# Power.net
KiCad netlist of a schematic drawn in Altium Designer
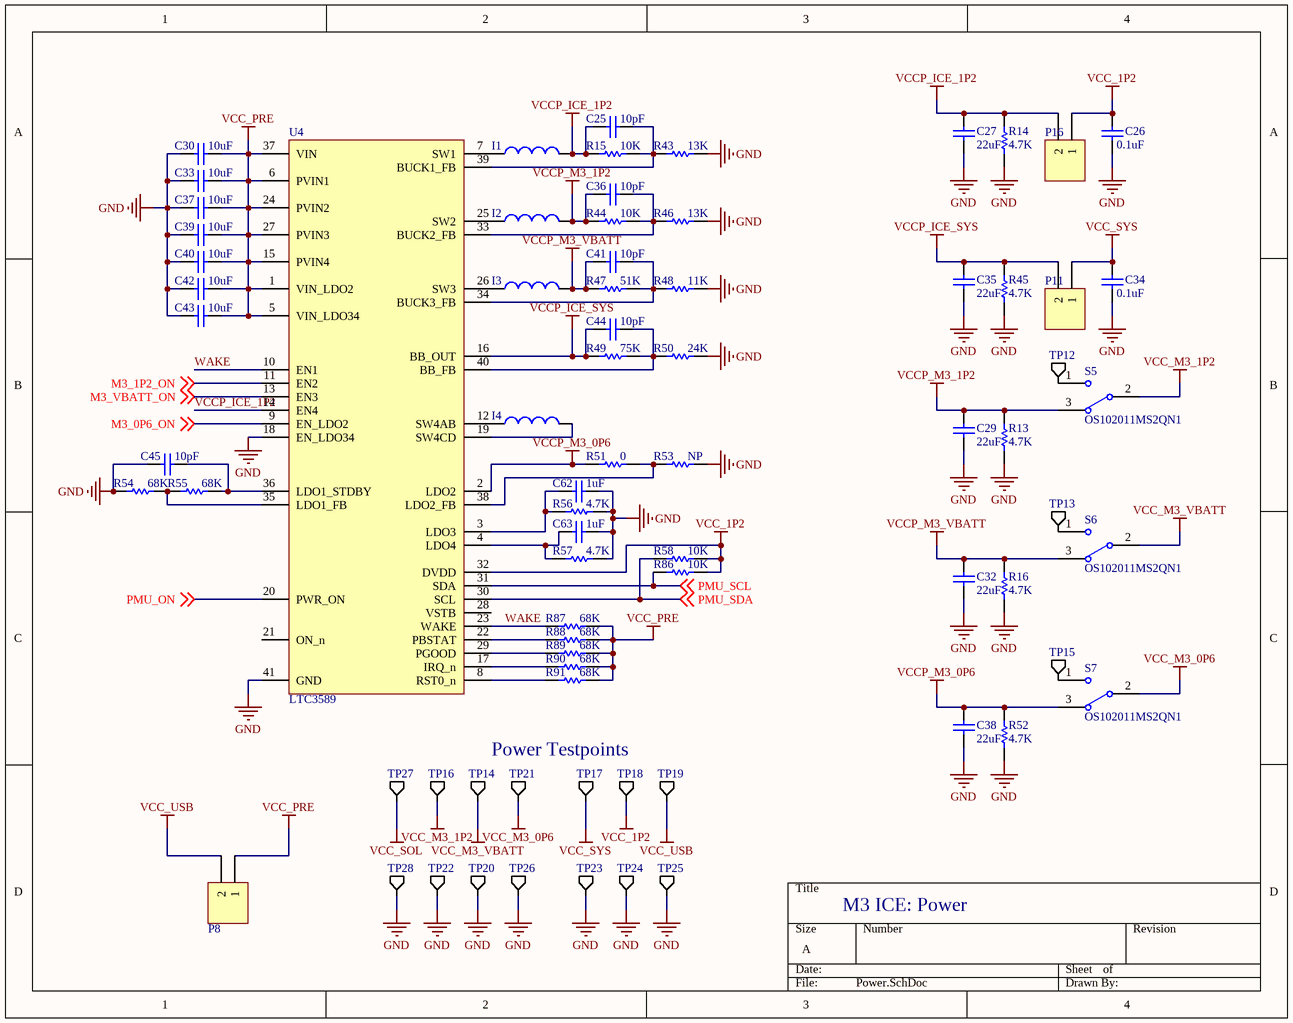
[diagram p0: Power.SchDoc]

(export (version "E")
  (design (tool "Eeschema 10.0.6"))
  (components
    (comp (ref "C25")
      (value "10pF")
      (footprint "0402")
      (description "Capacitor (Semiconductor SIM Model)")
      (fields
        (field (name "DISTPARTNO") "445-1235-1-ND")
        (field (name "MANPARTNO") "C1005C0G1H100D")
        (field (name "PUBLISHER") "Altium Limited")
      )
      (libsource (lib "Miscellaneous Devices") (part "Cap Semi"))
    )
    (comp (ref "C26")
      (value "0.1uF")
      (footprint "1608[0603]")
      (description "Capacitor (Semiconductor SIM Model)")
      (fields
        (field (name "DISTPARTNO") "445-1317-1-ND")
        (field (name "MANPARTNO") "C1608X7R1C104K")
        (field (name "PUBLISHER") "Altium Limited")
      )
      (libsource (lib "Miscellaneous Devices") (part "Cap Semi"))
    )
    (comp (ref "C27")
      (value "22uF")
      (footprint "0805")
      (description "Capacitor (Semiconductor SIM Model)")
      (fields
        (field (name "DISTPARTNO") "587-2782-1-ND")
        (field (name "MANPARTNO") "LMK316AB7226ML-TR")
        (field (name "PUBLISHER") "Altium Limited")
      )
      (libsource (lib "M3") (part "Cap Chip"))
    )
    (comp (ref "C29")
      (value "22uF")
      (footprint "0805")
      (description "Capacitor (Semiconductor SIM Model)")
      (fields
        (field (name "DISTPARTNO") "587-2782-1-ND")
        (field (name "MANPARTNO") "LMK316AB7226ML-TR")
        (field (name "PUBLISHER") "Altium Limited")
      )
      (libsource (lib "M3") (part "Cap Chip"))
    )
    (comp (ref "C30")
      (value "10uF")
      (footprint "0805")
      (description "Capacitor (Semiconductor SIM Model)")
      (fields
        (field (name "DISTPARTNO") "445-6857-1-ND")
        (field (name "MANPARTNO") "C2012X7R1A106K")
        (field (name "PUBLISHER") "Altium Limited")
      )
      (libsource (lib "M3") (part "Cap Chip"))
    )
    (comp (ref "C32")
      (value "22uF")
      (footprint "0805")
      (description "Capacitor (Semiconductor SIM Model)")
      (fields
        (field (name "DISTPARTNO") "587-2782-1-ND")
        (field (name "MANPARTNO") "LMK316AB7226ML-TR")
        (field (name "PUBLISHER") "Altium Limited")
      )
      (libsource (lib "M3") (part "Cap Chip"))
    )
    (comp (ref "C33")
      (value "10uF")
      (footprint "0805")
      (description "Capacitor (Semiconductor SIM Model)")
      (fields
        (field (name "DISTPARTNO") "445-6857-1-ND")
        (field (name "MANPARTNO") "C2012X7R1A106K")
        (field (name "PUBLISHER") "Altium Limited")
      )
      (libsource (lib "M3") (part "Cap Chip"))
    )
    (comp (ref "C34")
      (value "0.1uF")
      (footprint "1608[0603]")
      (description "Capacitor (Semiconductor SIM Model)")
      (fields
        (field (name "DISTPARTNO") "445-1317-1-ND")
        (field (name "MANPARTNO") "C1608X7R1C104K")
        (field (name "PUBLISHER") "Altium Limited")
      )
      (libsource (lib "Miscellaneous Devices") (part "Cap Semi"))
    )
    (comp (ref "C35")
      (value "22uF")
      (footprint "0805")
      (description "Capacitor (Semiconductor SIM Model)")
      (fields
        (field (name "DISTPARTNO") "587-2782-1-ND")
        (field (name "MANPARTNO") "LMK316AB7226ML-TR")
        (field (name "PUBLISHER") "Altium Limited")
      )
      (libsource (lib "M3") (part "Cap Chip"))
    )
    (comp (ref "C36")
      (value "10pF")
      (footprint "0402")
      (description "Capacitor (Semiconductor SIM Model)")
      (fields
        (field (name "DISTPARTNO") "445-1235-1-ND")
        (field (name "MANPARTNO") "C1005C0G1H100D")
        (field (name "PUBLISHER") "Altium Limited")
      )
      (libsource (lib "Miscellaneous Devices") (part "Cap Semi"))
    )
    (comp (ref "C37")
      (value "10uF")
      (footprint "0805")
      (description "Capacitor (Semiconductor SIM Model)")
      (fields
        (field (name "DISTPARTNO") "445-6857-1-ND")
        (field (name "MANPARTNO") "C2012X7R1A106K")
        (field (name "PUBLISHER") "Altium Limited")
      )
      (libsource (lib "M3") (part "Cap Chip"))
    )
    (comp (ref "C38")
      (value "22uF")
      (footprint "0805")
      (description "Capacitor (Semiconductor SIM Model)")
      (fields
        (field (name "DISTPARTNO") "587-2782-1-ND")
        (field (name "MANPARTNO") "LMK316AB7226ML-TR")
        (field (name "PUBLISHER") "Altium Limited")
      )
      (libsource (lib "M3") (part "Cap Chip"))
    )
    (comp (ref "C39")
      (value "10uF")
      (footprint "0805")
      (description "Capacitor (Semiconductor SIM Model)")
      (fields
        (field (name "DISTPARTNO") "445-6857-1-ND")
        (field (name "MANPARTNO") "C2012X7R1A106K")
        (field (name "PUBLISHER") "Altium Limited")
      )
      (libsource (lib "M3") (part "Cap Chip"))
    )
    (comp (ref "C40")
      (value "10uF")
      (footprint "0805")
      (description "Capacitor (Semiconductor SIM Model)")
      (fields
        (field (name "DISTPARTNO") "445-6857-1-ND")
        (field (name "MANPARTNO") "C2012X7R1A106K")
        (field (name "PUBLISHER") "Altium Limited")
      )
      (libsource (lib "M3") (part "Cap Chip"))
    )
    (comp (ref "C41")
      (value "10pF")
      (footprint "0402")
      (description "Capacitor (Semiconductor SIM Model)")
      (fields
        (field (name "DISTPARTNO") "445-1235-1-ND")
        (field (name "MANPARTNO") "C1005C0G1H100D")
        (field (name "PUBLISHER") "Altium Limited")
      )
      (libsource (lib "Miscellaneous Devices") (part "Cap Semi"))
    )
    (comp (ref "C42")
      (value "10uF")
      (footprint "0805")
      (description "Capacitor (Semiconductor SIM Model)")
      (fields
        (field (name "DISTPARTNO") "445-6857-1-ND")
        (field (name "MANPARTNO") "C2012X7R1A106K")
        (field (name "PUBLISHER") "Altium Limited")
      )
      (libsource (lib "M3") (part "Cap Chip"))
    )
    (comp (ref "C43")
      (value "10uF")
      (footprint "0805")
      (description "Capacitor (Semiconductor SIM Model)")
      (fields
        (field (name "DISTPARTNO") "445-6857-1-ND")
        (field (name "MANPARTNO") "C2012X7R1A106K")
        (field (name "PUBLISHER") "Altium Limited")
      )
      (libsource (lib "M3") (part "Cap Chip"))
    )
    (comp (ref "C44")
      (value "10pF")
      (footprint "0402")
      (description "Capacitor (Semiconductor SIM Model)")
      (fields
        (field (name "DISTPARTNO") "445-1235-1-ND")
        (field (name "MANPARTNO") "C1005C0G1H100D")
        (field (name "PUBLISHER") "Altium Limited")
      )
      (libsource (lib "Miscellaneous Devices") (part "Cap Semi"))
    )
    (comp (ref "C45")
      (value "10pF")
      (footprint "0402")
      (description "Capacitor (Semiconductor SIM Model)")
      (fields
        (field (name "DISTPARTNO") "445-1235-1-ND")
        (field (name "MANPARTNO") "C1005C0G1H100D")
        (field (name "PUBLISHER") "Altium Limited")
      )
      (libsource (lib "Miscellaneous Devices") (part "Cap Semi"))
    )
    (comp (ref "C62")
      (value "1uF")
      (footprint "0402")
      (description "Capacitor (Semiconductor SIM Model)")
      (fields
        (field (name "DISTPARTNO") "445-4991-1-ND")
        (field (name "MANPARTNO") "C1005X5R1A105M")
        (field (name "PUBLISHER") "Altium Limited")
      )
      (libsource (lib "Miscellaneous Devices") (part "Cap Semi"))
    )
    (comp (ref "C63")
      (value "1uF")
      (footprint "0402")
      (description "Capacitor (Semiconductor SIM Model)")
      (fields
        (field (name "DISTPARTNO") "445-4991-1-ND")
        (field (name "MANPARTNO") "C1005X5R1A105M")
        (field (name "PUBLISHER") "Altium Limited")
      )
      (libsource (lib "Miscellaneous Devices") (part "Cap Semi"))
    )
    (comp (ref "I1")
      (value "NR5040T1R5N")
      (footprint "INDUCTOR_.118x.142mm")
      (fields (field (name "DISTPARTNO") "541-1327-1-ND") (field (name "MANPARTNO") "IHLP1212AEER1R0M11"))
      (libsource (lib "M3") (part "IHLP1212"))
    )
    (comp (ref "I2")
      (value "NR5040T1R5N")
      (footprint "INDUCTOR_.118x.142mm")
      (fields (field (name "DISTPARTNO") "541-1327-1-ND") (field (name "MANPARTNO") "IHLP1212AEER1R0M11"))
      (libsource (lib "M3") (part "IHLP1212"))
    )
    (comp (ref "I3")
      (value "NR5040T1R5N")
      (footprint "INDUCTOR_.118x.142mm")
      (fields (field (name "DISTPARTNO") "541-1327-1-ND") (field (name "MANPARTNO") "IHLP1212AEER1R0M11"))
      (libsource (lib "M3") (part "IHLP1212"))
    )
    (comp (ref "I4")
      (value "NR5040T1R5N")
      (footprint "INDUCTOR_.118x.142mm")
      (fields (field (name "DISTPARTNO") "541-1327-1-ND") (field (name "MANPARTNO") "IHLP1212AEER1R0M11"))
      (libsource (lib "M3") (part "IHLP1212"))
    )
    (comp (ref "P8")
      (value "Header 2")
      (footprint "HDR1X2")
      (description "Header, 2-Pin")
      (fields (field (name "PUBLISHER") "Altium Limited"))
      (libsource (lib "Miscellaneous Connectors") (part "Header 2"))
    )
    (comp (ref "P11")
      (value "Header 2")
      (footprint "HDR1X2")
      (description "Header, 2-Pin")
      (fields (field (name "PUBLISHER") "Altium Limited"))
      (libsource (lib "Miscellaneous Connectors") (part "Header 2"))
    )
    (comp (ref "P16")
      (value "Header 2")
      (footprint "HDR1X2")
      (description "Header, 2-Pin")
      (fields (field (name "PUBLISHER") "Altium Limited"))
      (libsource (lib "Miscellaneous Connectors") (part "Header 2"))
    )
    (comp (ref "R13")
      (value "4.7K")
      (footprint "0603")
      (description "Semiconductor Resistor")
      (fields
        (field (name "DISTPARTNO") "P4.7KGCT-ND")
        (field (name "MANPARTNO") "ERJ-3GEYJ472V")
        (field (name "PUBLISHER") "Altium Limited")
      )
      (libsource (lib "M3") (part "Res Chip"))
    )
    (comp (ref "R14")
      (value "4.7K")
      (footprint "0603")
      (description "Semiconductor Resistor")
      (fields
        (field (name "DISTPARTNO") "P4.7KGCT-ND")
        (field (name "MANPARTNO") "ERJ-3GEYJ472V")
        (field (name "PUBLISHER") "Altium Limited")
      )
      (libsource (lib "M3") (part "Res Chip"))
    )
    (comp (ref "R15")
      (value "10K")
      (footprint "0402")
      (description "Semiconductor Resistor")
      (fields
        (field (name "DISTPARTNO") "P10.0KLCT-ND")
        (field (name "MANPARTNO") "ERJ-2RKF1002X")
        (field (name "PUBLISHER") "Altium Limited")
      )
      (libsource (lib "M3") (part "Res Chip"))
    )
    (comp (ref "R16")
      (value "4.7K")
      (footprint "0603")
      (description "Semiconductor Resistor")
      (fields
        (field (name "DISTPARTNO") "P4.7KGCT-ND")
        (field (name "MANPARTNO") "ERJ-3GEYJ472V")
        (field (name "PUBLISHER") "Altium Limited")
      )
      (libsource (lib "M3") (part "Res Chip"))
    )
    (comp (ref "R43")
      (value "13K")
      (footprint "0402")
      (description "Semiconductor Resistor")
      (fields
        (field (name "DISTPARTNO") "311-13.0KLRCT-ND")
        (field (name "MANPARTNO") "RC0402FR-0713KL")
        (field (name "PUBLISHER") "Altium Limited")
      )
      (libsource (lib "M3") (part "Res Chip"))
    )
    (comp (ref "R44")
      (value "10K")
      (footprint "0402")
      (description "Semiconductor Resistor")
      (fields
        (field (name "DISTPARTNO") "P10.0KLCT-ND")
        (field (name "MANPARTNO") "ERJ-2RKF1002X")
        (field (name "PUBLISHER") "Altium Limited")
      )
      (libsource (lib "M3") (part "Res Chip"))
    )
    (comp (ref "R45")
      (value "4.7K")
      (footprint "0603")
      (description "Semiconductor Resistor")
      (fields
        (field (name "DISTPARTNO") "P4.7KGCT-ND")
        (field (name "MANPARTNO") "ERJ-3GEYJ472V")
        (field (name "PUBLISHER") "Altium Limited")
      )
      (libsource (lib "M3") (part "Res Chip"))
    )
    (comp (ref "R46")
      (value "13K")
      (footprint "0402")
      (description "Semiconductor Resistor")
      (fields
        (field (name "DISTPARTNO") "311-13.0KLRCT-ND")
        (field (name "MANPARTNO") "RC0402FR-0713KL")
        (field (name "PUBLISHER") "Altium Limited")
      )
      (libsource (lib "M3") (part "Res Chip"))
    )
    (comp (ref "R47")
      (value "51K")
      (footprint "0402")
      (description "Semiconductor Resistor")
      (fields
        (field (name "DISTPARTNO") "P51.0KLCT-ND")
        (field (name "MANPARTNO") "ERJ-2RKF5102X")
        (field (name "PUBLISHER") "Altium Limited")
      )
      (libsource (lib "M3") (part "Res Chip"))
    )
    (comp (ref "R48")
      (value "11K")
      (footprint "0402")
      (description "Semiconductor Resistor")
      (fields
        (field (name "DISTPARTNO") "P11.0KLCT-ND")
        (field (name "MANPARTNO") "ERJ-2RKF1102X")
        (field (name "PUBLISHER") "Altium Limited")
      )
      (libsource (lib "M3") (part "Res Chip"))
    )
    (comp (ref "R49")
      (value "75K")
      (footprint "0402")
      (description "Semiconductor Resistor")
      (fields
        (field (name "DISTPARTNO") "P75.0KLCT-ND")
        (field (name "MANPARTNO") "ERJ-2RKF7502X")
        (field (name "PUBLISHER") "Altium Limited")
      )
      (libsource (lib "M3") (part "Res Chip"))
    )
    (comp (ref "R50")
      (value "24K")
      (footprint "0402")
      (description "Semiconductor Resistor")
      (fields
        (field (name "DISTPARTNO") "RMCF0402FT24K0CT-ND")
        (field (name "MANPARTNO") "RMCF0402FT24K0")
        (field (name "PUBLISHER") "Altium Limited")
      )
      (libsource (lib "M3") (part "Res Chip"))
    )
    (comp (ref "R51")
      (value "0")
      (footprint "0402")
      (description "Semiconductor Resistor")
      (fields
        (field (name "DISTPARTNO") "P0.0JCT-ND")
        (field (name "MANPARTNO") "ERJ-2GE0R00X")
        (field (name "PUBLISHER") "Altium Limited")
      )
      (libsource (lib "M3") (part "Res Chip"))
    )
    (comp (ref "R52")
      (value "4.7K")
      (footprint "0603")
      (description "Semiconductor Resistor")
      (fields
        (field (name "DISTPARTNO") "P4.7KGCT-ND")
        (field (name "MANPARTNO") "ERJ-3GEYJ472V")
        (field (name "PUBLISHER") "Altium Limited")
      )
      (libsource (lib "M3") (part "Res Chip"))
    )
    (comp (ref "R53")
      (value "NP")
      (footprint "0402")
      (description "Semiconductor Resistor")
      (fields (field (name "Comment") "Res Chip") (field (name "PUBLISHER") "Altium Limited"))
      (libsource (lib "M3") (part "Res Chip"))
    )
    (comp (ref "R54")
      (value "68K")
      (footprint "0402")
      (description "Semiconductor Resistor")
      (fields
        (field (name "DISTPARTNO") "P68.0KLCT-ND")
        (field (name "MANPARTNO") "ERJ-2RKF6802X")
        (field (name "PUBLISHER") "Altium Limited")
      )
      (libsource (lib "M3") (part "Res Chip"))
    )
    (comp (ref "R55")
      (value "68K")
      (footprint "0402")
      (description "Semiconductor Resistor")
      (fields
        (field (name "DISTPARTNO") "P68.0KLCT-ND")
        (field (name "MANPARTNO") "ERJ-2RKF6802X")
        (field (name "PUBLISHER") "Altium Limited")
      )
      (libsource (lib "M3") (part "Res Chip"))
    )
    (comp (ref "R56")
      (value "4.7K")
      (footprint "0402")
      (description "Semiconductor Resistor")
      (fields
        (field (name "DISTPARTNO") "P4.70KLCT-ND")
        (field (name "MANPARTNO") "ERJ-2RKF4701X")
        (field (name "PUBLISHER") "Altium Limited")
      )
      (libsource (lib "M3") (part "Res Chip"))
    )
    (comp (ref "R57")
      (value "4.7K")
      (footprint "0402")
      (description "Semiconductor Resistor")
      (fields
        (field (name "DISTPARTNO") "P4.70KLCT-ND")
        (field (name "MANPARTNO") "ERJ-2RKF4701X")
        (field (name "PUBLISHER") "Altium Limited")
      )
      (libsource (lib "M3") (part "Res Chip"))
    )
    (comp (ref "R58")
      (value "10K")
      (footprint "0402")
      (description "Semiconductor Resistor")
      (fields
        (field (name "DISTPARTNO") "P10.0KLCT-ND")
        (field (name "MANPARTNO") "ERJ-2RKF1002X")
        (field (name "PUBLISHER") "Altium Limited")
      )
      (libsource (lib "M3") (part "Res Chip"))
    )
    (comp (ref "R86")
      (value "10K")
      (footprint "0402")
      (description "Semiconductor Resistor")
      (fields
        (field (name "DISTPARTNO") "P10.0KLCT-ND")
        (field (name "MANPARTNO") "ERJ-2RKF1002X")
        (field (name "PUBLISHER") "Altium Limited")
      )
      (libsource (lib "M3") (part "Res Chip"))
    )
    (comp (ref "R87")
      (value "68K")
      (footprint "0402")
      (description "Semiconductor Resistor")
      (fields
        (field (name "DISTPARTNO") "P68.0KLCT-ND")
        (field (name "MANPARTNO") "ERJ-2RKF6802X")
        (field (name "PUBLISHER") "Altium Limited")
      )
      (libsource (lib "M3") (part "Res Chip"))
    )
    (comp (ref "R88")
      (value "68K")
      (footprint "0402")
      (description "Semiconductor Resistor")
      (fields
        (field (name "DISTPARTNO") "P68.0KLCT-ND")
        (field (name "MANPARTNO") "ERJ-2RKF6802X")
        (field (name "PUBLISHER") "Altium Limited")
      )
      (libsource (lib "M3") (part "Res Chip"))
    )
    (comp (ref "R89")
      (value "68K")
      (footprint "0402")
      (description "Semiconductor Resistor")
      (fields
        (field (name "DISTPARTNO") "P68.0KLCT-ND")
        (field (name "MANPARTNO") "ERJ-2RKF6802X")
        (field (name "PUBLISHER") "Altium Limited")
      )
      (libsource (lib "M3") (part "Res Chip"))
    )
    (comp (ref "R90")
      (value "68K")
      (footprint "0402")
      (description "Semiconductor Resistor")
      (fields
        (field (name "DISTPARTNO") "P68.0KLCT-ND")
        (field (name "MANPARTNO") "ERJ-2RKF6802X")
        (field (name "PUBLISHER") "Altium Limited")
      )
      (libsource (lib "M3") (part "Res Chip"))
    )
    (comp (ref "R91")
      (value "68K")
      (footprint "0402")
      (description "Semiconductor Resistor")
      (fields
        (field (name "DISTPARTNO") "P68.0KLCT-ND")
        (field (name "MANPARTNO") "ERJ-2RKF6802X")
        (field (name "PUBLISHER") "Altium Limited")
      )
      (libsource (lib "M3") (part "Res Chip"))
    )
    (comp (ref "S5")
      (value "OS102011MS2QN1")
      (footprint "SPDT_SW2")
      (description "SPDT Slide Switch")
      (fields (field (name "DISTPARTNO") "CKN9565-ND"))
      (libsource (lib "M3") (part "OS102011MS2QN1"))
    )
    (comp (ref "S6")
      (value "OS102011MS2QN1")
      (footprint "SPDT_SW2")
      (description "SPDT Slide Switch")
      (fields (field (name "DISTPARTNO") "CKN9565-ND"))
      (libsource (lib "M3") (part "OS102011MS2QN1"))
    )
    (comp (ref "S7")
      (value "OS102011MS2QN1")
      (footprint "SPDT_SW2")
      (description "SPDT Slide Switch")
      (fields (field (name "DISTPARTNO") "CKN9565-ND"))
      (libsource (lib "M3") (part "OS102011MS2QN1"))
    )
    (comp (ref "TP12") (value "TP") (footprint "TP") (libsource (lib "M3") (part "TP")))
    (comp (ref "TP13") (value "TP") (footprint "TP") (libsource (lib "M3") (part "TP")))
    (comp (ref "TP14") (value "TP") (footprint "TP") (libsource (lib "M3") (part "TP")))
    (comp (ref "TP15") (value "TP") (footprint "TP") (libsource (lib "M3") (part "TP")))
    (comp (ref "TP16") (value "TP") (footprint "TP") (libsource (lib "M3") (part "TP")))
    (comp (ref "TP17") (value "TP") (footprint "TP") (libsource (lib "M3") (part "TP")))
    (comp (ref "TP18") (value "TP") (footprint "TP") (libsource (lib "M3") (part "TP")))
    (comp (ref "TP19") (value "TP") (footprint "TP") (libsource (lib "M3") (part "TP")))
    (comp (ref "TP20") (value "TP") (footprint "TP") (libsource (lib "M3") (part "TP")))
    (comp (ref "TP21") (value "TP") (footprint "TP") (libsource (lib "M3") (part "TP")))
    (comp (ref "TP22") (value "TP") (footprint "TP") (libsource (lib "M3") (part "TP")))
    (comp (ref "TP23") (value "TP") (footprint "TP") (libsource (lib "M3") (part "TP")))
    (comp (ref "TP24") (value "TP") (footprint "TP") (libsource (lib "M3") (part "TP")))
    (comp (ref "TP25") (value "TP") (footprint "TP") (libsource (lib "M3") (part "TP")))
    (comp (ref "TP26") (value "TP") (footprint "TP") (libsource (lib "M3") (part "TP")))
    (comp (ref "TP27") (value "TP") (footprint "TP") (libsource (lib "M3") (part "TP")))
    (comp (ref "TP28") (value "TP") (footprint "TP") (libsource (lib "M3") (part "TP")))
    (comp (ref "U4")
      (value "LTC3589")
      (footprint "QFN-40")
      (fields (field (name "DISTPARTNO") "LTC3589EUJ-2#PBF-ND") (field (name "MANPARTNO") "LTC3589EUJ-2#PBF"))
      (libsource (lib "M3") (part "LTC3589"))
    )
  )
  (nets
    (net (code "1") (name "/WAKE") (class "Default")
      (node (ref "R87") (pin "1") (pinfunction "1_1") (pintype "passive"))
      (node (ref "U4") (pin "10") (pinfunction "EN1_10") (pintype "passive"))
      (node (ref "U4") (pin "23") (pinfunction "WAKE_23") (pintype "passive"))
    )
    (net (code "2") (name "GND") (class "Default")
      (node (ref "C26") (pin "1") (pinfunction "1_1") (pintype "passive"))
      (node (ref "C27") (pin "1") (pinfunction "1_1") (pintype "passive"))
      (node (ref "C29") (pin "1") (pinfunction "1_1") (pintype "passive"))
      (node (ref "C30") (pin "2") (pinfunction "2_2") (pintype "passive"))
      (node (ref "C32") (pin "1") (pinfunction "1_1") (pintype "passive"))
      (node (ref "C33") (pin "2") (pinfunction "2_2") (pintype "passive"))
      (node (ref "C34") (pin "1") (pinfunction "1_1") (pintype "passive"))
      (node (ref "C35") (pin "1") (pinfunction "1_1") (pintype "passive"))
      (node (ref "C37") (pin "2") (pinfunction "2_2") (pintype "passive"))
      (node (ref "C38") (pin "1") (pinfunction "1_1") (pintype "passive"))
      (node (ref "C39") (pin "2") (pinfunction "2_2") (pintype "passive"))
      (node (ref "C40") (pin "2") (pinfunction "2_2") (pintype "passive"))
      (node (ref "C42") (pin "2") (pinfunction "2_2") (pintype "passive"))
      (node (ref "C43") (pin "2") (pinfunction "2_2") (pintype "passive"))
      (node (ref "C45") (pin "2") (pinfunction "2_2") (pintype "passive"))
      (node (ref "C62") (pin "1") (pinfunction "1_1") (pintype "passive"))
      (node (ref "C63") (pin "1") (pinfunction "1_1") (pintype "passive"))
      (node (ref "R13") (pin "1") (pinfunction "1_1") (pintype "passive"))
      (node (ref "R14") (pin "1") (pinfunction "1_1") (pintype "passive"))
      (node (ref "R16") (pin "1") (pinfunction "1_1") (pintype "passive"))
      (node (ref "R43") (pin "2") (pinfunction "2_2") (pintype "passive"))
      (node (ref "R45") (pin "1") (pinfunction "1_1") (pintype "passive"))
      (node (ref "R46") (pin "2") (pinfunction "2_2") (pintype "passive"))
      (node (ref "R48") (pin "2") (pinfunction "2_2") (pintype "passive"))
      (node (ref "R50") (pin "2") (pinfunction "2_2") (pintype "passive"))
      (node (ref "R52") (pin "1") (pinfunction "1_1") (pintype "passive"))
      (node (ref "R53") (pin "2") (pinfunction "2_2") (pintype "passive"))
      (node (ref "R54") (pin "1") (pinfunction "1_1") (pintype "passive"))
      (node (ref "R56") (pin "2") (pinfunction "2_2") (pintype "passive"))
      (node (ref "R57") (pin "2") (pinfunction "2_2") (pintype "passive"))
      (node (ref "TP20") (pin "1") (pinfunction "A_1") (pintype "passive"))
      (node (ref "TP22") (pin "1") (pinfunction "A_1") (pintype "passive"))
      (node (ref "TP23") (pin "1") (pinfunction "A_1") (pintype "passive"))
      (node (ref "TP24") (pin "1") (pinfunction "A_1") (pintype "passive"))
      (node (ref "TP25") (pin "1") (pinfunction "A_1") (pintype "passive"))
      (node (ref "TP26") (pin "1") (pinfunction "A_1") (pintype "passive"))
      (node (ref "TP28") (pin "1") (pinfunction "A_1") (pintype "passive"))
      (node (ref "U4") (pin "18") (pinfunction "EN_LDO34_18") (pintype "passive"))
      (node (ref "U4") (pin "41") (pinfunction "GND_41") (pintype "passive"))
    )
    (net (code "3") (name "M3_0P6_ON") (class "Default")
      (node (ref "U4") (pin "9") (pinfunction "EN_LDO2_9") (pintype "passive"))
    )
    (net (code "4") (name "M3_1P2_ON") (class "Default")
      (node (ref "U4") (pin "11") (pinfunction "EN2_11") (pintype "passive"))
    )
    (net (code "5") (name "M3_VBATT_ON") (class "Default")
      (node (ref "U4") (pin "13") (pinfunction "EN3_13") (pintype "passive"))
    )
    (net (code "6") (name "Net-(TP12-A)") (class "Default")
      (node (ref "S5") (pin "1") (pinfunction "1_1") (pintype "passive"))
      (node (ref "TP12") (pin "1") (pinfunction "A_1") (pintype "passive"))
    )
    (net (code "7") (name "Net-(TP13-A)") (class "Default")
      (node (ref "S6") (pin "1") (pinfunction "1_1") (pintype "passive"))
      (node (ref "TP13") (pin "1") (pinfunction "A_1") (pintype "passive"))
    )
    (net (code "8") (name "Net-(TP15-A)") (class "Default")
      (node (ref "S7") (pin "1") (pinfunction "1_1") (pintype "passive"))
      (node (ref "TP15") (pin "1") (pinfunction "A_1") (pintype "passive"))
    )
    (net (code "9") (name "Net-(U4-BB_FB)") (class "Default")
      (node (ref "C44") (pin "1") (pinfunction "1_1") (pintype "passive"))
      (node (ref "R49") (pin "2") (pinfunction "2_2") (pintype "passive"))
      (node (ref "R50") (pin "1") (pinfunction "1_1") (pintype "passive"))
      (node (ref "U4") (pin "40") (pinfunction "BB_FB_40") (pintype "passive"))
    )
    (net (code "10") (name "Net-(U4-BUCK1_FB)") (class "Default")
      (node (ref "C25") (pin "1") (pinfunction "1_1") (pintype "passive"))
      (node (ref "R15") (pin "2") (pinfunction "2_2") (pintype "passive"))
      (node (ref "R43") (pin "1") (pinfunction "1_1") (pintype "passive"))
      (node (ref "U4") (pin "39") (pinfunction "BUCK1_FB_39") (pintype "passive"))
    )
    (net (code "11") (name "Net-(U4-BUCK2_FB)") (class "Default")
      (node (ref "C36") (pin "1") (pinfunction "1_1") (pintype "passive"))
      (node (ref "R44") (pin "2") (pinfunction "2_2") (pintype "passive"))
      (node (ref "R46") (pin "1") (pinfunction "1_1") (pintype "passive"))
      (node (ref "U4") (pin "33") (pinfunction "BUCK2_FB_33") (pintype "passive"))
    )
    (net (code "12") (name "Net-(U4-BUCK3_FB)") (class "Default")
      (node (ref "C41") (pin "1") (pinfunction "1_1") (pintype "passive"))
      (node (ref "R47") (pin "2") (pinfunction "2_2") (pintype "passive"))
      (node (ref "R48") (pin "1") (pinfunction "1_1") (pintype "passive"))
      (node (ref "U4") (pin "34") (pinfunction "BUCK3_FB_34") (pintype "passive"))
    )
    (net (code "13") (name "Net-(U4-IRQ_n)") (class "Default")
      (node (ref "R90") (pin "1") (pinfunction "1_1") (pintype "passive"))
      (node (ref "U4") (pin "17") (pinfunction "IRQ_n_17") (pintype "passive"))
    )
    (net (code "14") (name "Net-(U4-LDO1_FB)") (class "Default")
      (node (ref "R54") (pin "2") (pinfunction "2_2") (pintype "passive"))
      (node (ref "R55") (pin "1") (pinfunction "1_1") (pintype "passive"))
      (node (ref "U4") (pin "35") (pinfunction "LDO1_FB_35") (pintype "passive"))
    )
    (net (code "15") (name "Net-(U4-LDO1_STDBY)") (class "Default")
      (node (ref "C45") (pin "1") (pinfunction "1_1") (pintype "passive"))
      (node (ref "R55") (pin "2") (pinfunction "2_2") (pintype "passive"))
      (node (ref "U4") (pin "36") (pinfunction "LDO1_STDBY_36") (pintype "passive"))
    )
    (net (code "16") (name "Net-(U4-LDO2_FB)") (class "Default")
      (node (ref "R51") (pin "2") (pinfunction "2_2") (pintype "passive"))
      (node (ref "R53") (pin "1") (pinfunction "1_1") (pintype "passive"))
      (node (ref "U4") (pin "38") (pinfunction "LDO2_FB_38") (pintype "passive"))
    )
    (net (code "17") (name "Net-(U4-LDO3)") (class "Default")
      (node (ref "C62") (pin "2") (pinfunction "2_2") (pintype "passive"))
      (node (ref "R56") (pin "1") (pinfunction "1_1") (pintype "passive"))
      (node (ref "U4") (pin "3") (pinfunction "LDO3_3") (pintype "passive"))
    )
    (net (code "18") (name "Net-(U4-LDO4)") (class "Default")
      (node (ref "C63") (pin "2") (pinfunction "2_2") (pintype "passive"))
      (node (ref "R57") (pin "1") (pinfunction "1_1") (pintype "passive"))
      (node (ref "U4") (pin "4") (pinfunction "LDO4_4") (pintype "passive"))
    )
    (net (code "19") (name "Net-(U4-PBSTAT)") (class "Default")
      (node (ref "R88") (pin "1") (pinfunction "1_1") (pintype "passive"))
      (node (ref "U4") (pin "22") (pinfunction "PBSTAT_22") (pintype "passive"))
    )
    (net (code "20") (name "Net-(U4-PGOOD)") (class "Default")
      (node (ref "R89") (pin "1") (pinfunction "1_1") (pintype "passive"))
      (node (ref "U4") (pin "29") (pinfunction "PGOOD_29") (pintype "passive"))
    )
    (net (code "21") (name "Net-(U4-RST0_n)") (class "Default")
      (node (ref "R91") (pin "1") (pinfunction "1_1") (pintype "passive"))
      (node (ref "U4") (pin "8") (pinfunction "RST0_n_8") (pintype "passive"))
    )
    (net (code "22") (name "Net-(U4-SW1)") (class "Default")
      (node (ref "I1") (pin "1") (pinfunction "1_1") (pintype "passive"))
      (node (ref "U4") (pin "7") (pinfunction "SW1_7") (pintype "passive"))
    )
    (net (code "23") (name "Net-(U4-SW2)") (class "Default")
      (node (ref "I2") (pin "1") (pinfunction "1_1") (pintype "passive"))
      (node (ref "U4") (pin "25") (pinfunction "SW2_25") (pintype "passive"))
    )
    (net (code "24") (name "Net-(U4-SW3)") (class "Default")
      (node (ref "I3") (pin "1") (pinfunction "1_1") (pintype "passive"))
      (node (ref "U4") (pin "26") (pinfunction "SW3_26") (pintype "passive"))
    )
    (net (code "25") (name "Net-(U4-SW4AB)") (class "Default")
      (node (ref "I4") (pin "1") (pinfunction "1_1") (pintype "passive"))
      (node (ref "U4") (pin "12") (pinfunction "SW4AB_12") (pintype "passive"))
    )
    (net (code "26") (name "Net-(U4-SW4CD)") (class "Default")
      (node (ref "I4") (pin "2") (pinfunction "2_2") (pintype "passive"))
      (node (ref "U4") (pin "19") (pinfunction "SW4CD_19") (pintype "passive"))
    )
    (net (code "27") (name "PMU_ON") (class "Default")
      (node (ref "U4") (pin "20") (pinfunction "PWR_ON_20") (pintype "passive"))
    )
    (net (code "28") (name "PMU_SCL") (class "Default")
      (node (ref "R86") (pin "1") (pinfunction "1_1") (pintype "passive"))
      (node (ref "U4") (pin "31") (pinfunction "SDA_31") (pintype "passive"))
    )
    (net (code "29") (name "PMU_SDA") (class "Default")
      (node (ref "R58") (pin "1") (pinfunction "1_1") (pintype "passive"))
      (node (ref "U4") (pin "30") (pinfunction "SCL_30") (pintype "passive"))
    )
    (net (code "30") (name "VCCP_ICE_1P2") (class "Default")
      (node (ref "C25") (pin "2") (pinfunction "2_2") (pintype "passive"))
      (node (ref "C27") (pin "2") (pinfunction "2_2") (pintype "passive"))
      (node (ref "I1") (pin "2") (pinfunction "2_2") (pintype "passive"))
      (node (ref "P16") (pin "2") (pinfunction "2_2") (pintype "passive"))
      (node (ref "R14") (pin "2") (pinfunction "2_2") (pintype "passive"))
      (node (ref "R15") (pin "1") (pinfunction "1_1") (pintype "passive"))
      (node (ref "U4") (pin "14") (pinfunction "EN4_14") (pintype "passive"))
    )
    (net (code "31") (name "VCCP_ICE_SYS") (class "Default")
      (node (ref "C35") (pin "2") (pinfunction "2_2") (pintype "passive"))
      (node (ref "C44") (pin "2") (pinfunction "2_2") (pintype "passive"))
      (node (ref "P11") (pin "2") (pinfunction "2_2") (pintype "passive"))
      (node (ref "R45") (pin "2") (pinfunction "2_2") (pintype "passive"))
      (node (ref "R49") (pin "1") (pinfunction "1_1") (pintype "passive"))
      (node (ref "U4") (pin "16") (pinfunction "BB_OUT_16") (pintype "passive"))
    )
    (net (code "32") (name "VCCP_M3_0P6") (class "Default")
      (node (ref "C38") (pin "2") (pinfunction "2_2") (pintype "passive"))
      (node (ref "R51") (pin "1") (pinfunction "1_1") (pintype "passive"))
      (node (ref "R52") (pin "2") (pinfunction "2_2") (pintype "passive"))
      (node (ref "S7") (pin "3") (pinfunction "3_3") (pintype "passive"))
      (node (ref "U4") (pin "2") (pinfunction "LDO2_2") (pintype "passive"))
    )
    (net (code "33") (name "VCCP_M3_1P2") (class "Default")
      (node (ref "C29") (pin "2") (pinfunction "2_2") (pintype "passive"))
      (node (ref "C36") (pin "2") (pinfunction "2_2") (pintype "passive"))
      (node (ref "I2") (pin "2") (pinfunction "2_2") (pintype "passive"))
      (node (ref "R13") (pin "2") (pinfunction "2_2") (pintype "passive"))
      (node (ref "R44") (pin "1") (pinfunction "1_1") (pintype "passive"))
      (node (ref "S5") (pin "3") (pinfunction "3_3") (pintype "passive"))
    )
    (net (code "34") (name "VCCP_M3_VBATT") (class "Default")
      (node (ref "C32") (pin "2") (pinfunction "2_2") (pintype "passive"))
      (node (ref "C41") (pin "2") (pinfunction "2_2") (pintype "passive"))
      (node (ref "I3") (pin "2") (pinfunction "2_2") (pintype "passive"))
      (node (ref "R16") (pin "2") (pinfunction "2_2") (pintype "passive"))
      (node (ref "R47") (pin "1") (pinfunction "1_1") (pintype "passive"))
      (node (ref "S6") (pin "3") (pinfunction "3_3") (pintype "passive"))
    )
    (net (code "35") (name "VCC_1P2") (class "Default")
      (node (ref "C26") (pin "2") (pinfunction "2_2") (pintype "passive"))
      (node (ref "P16") (pin "1") (pinfunction "1_1") (pintype "passive"))
      (node (ref "R58") (pin "2") (pinfunction "2_2") (pintype "passive"))
      (node (ref "R86") (pin "2") (pinfunction "2_2") (pintype "passive"))
      (node (ref "TP18") (pin "1") (pinfunction "A_1") (pintype "passive"))
      (node (ref "U4") (pin "32") (pinfunction "DVDD_32") (pintype "passive"))
    )
    (net (code "36") (name "VCC_M3_0P6") (class "Default")
      (node (ref "S7") (pin "2") (pinfunction "2_2") (pintype "passive"))
      (node (ref "TP21") (pin "1") (pinfunction "A_1") (pintype "passive"))
    )
    (net (code "37") (name "VCC_M3_1P2") (class "Default")
      (node (ref "S5") (pin "2") (pinfunction "2_2") (pintype "passive"))
      (node (ref "TP16") (pin "1") (pinfunction "A_1") (pintype "passive"))
    )
    (net (code "38") (name "VCC_M3_VBATT") (class "Default")
      (node (ref "S6") (pin "2") (pinfunction "2_2") (pintype "passive"))
      (node (ref "TP14") (pin "1") (pinfunction "A_1") (pintype "passive"))
    )
    (net (code "39") (name "VCC_PRE") (class "Default")
      (node (ref "C30") (pin "1") (pinfunction "1_1") (pintype "passive"))
      (node (ref "C33") (pin "1") (pinfunction "1_1") (pintype "passive"))
      (node (ref "C37") (pin "1") (pinfunction "1_1") (pintype "passive"))
      (node (ref "C39") (pin "1") (pinfunction "1_1") (pintype "passive"))
      (node (ref "C40") (pin "1") (pinfunction "1_1") (pintype "passive"))
      (node (ref "C42") (pin "1") (pinfunction "1_1") (pintype "passive"))
      (node (ref "C43") (pin "1") (pinfunction "1_1") (pintype "passive"))
      (node (ref "P8") (pin "1") (pinfunction "1_1") (pintype "passive"))
      (node (ref "R87") (pin "2") (pinfunction "2_2") (pintype "passive"))
      (node (ref "R88") (pin "2") (pinfunction "2_2") (pintype "passive"))
      (node (ref "R89") (pin "2") (pinfunction "2_2") (pintype "passive"))
      (node (ref "R90") (pin "2") (pinfunction "2_2") (pintype "passive"))
      (node (ref "R91") (pin "2") (pinfunction "2_2") (pintype "passive"))
      (node (ref "U4") (pin "1") (pinfunction "VIN_LDO2_1") (pintype "passive"))
      (node (ref "U4") (pin "15") (pinfunction "PVIN4_15") (pintype "passive"))
      (node (ref "U4") (pin "24") (pinfunction "PVIN2_24") (pintype "passive"))
      (node (ref "U4") (pin "27") (pinfunction "PVIN3_27") (pintype "passive"))
      (node (ref "U4") (pin "37") (pinfunction "VIN_37") (pintype "passive"))
      (node (ref "U4") (pin "5") (pinfunction "VIN_LDO34_5") (pintype "passive"))
      (node (ref "U4") (pin "6") (pinfunction "PVIN1_6") (pintype "passive"))
    )
    (net (code "40") (name "VCC_SOL") (class "Default")
      (node (ref "TP27") (pin "1") (pinfunction "A_1") (pintype "passive"))
    )
    (net (code "41") (name "VCC_SYS") (class "Default")
      (node (ref "C34") (pin "2") (pinfunction "2_2") (pintype "passive"))
      (node (ref "P11") (pin "1") (pinfunction "1_1") (pintype "passive"))
      (node (ref "TP17") (pin "1") (pinfunction "A_1") (pintype "passive"))
    )
    (net (code "42") (name "VCC_USB") (class "Default")
      (node (ref "P8") (pin "2") (pinfunction "2_2") (pintype "passive"))
      (node (ref "TP19") (pin "1") (pinfunction "A_1") (pintype "passive"))
    )
    (net (code "43") (name "unconnected-(U4-ON_n-Pad21)") (class "Default")
      (node (ref "U4") (pin "21") (pinfunction "ON_n_21") (pintype "passive"))
    )
    (net (code "44") (name "unconnected-(U4-VSTB-Pad28)") (class "Default")
      (node (ref "U4") (pin "28") (pinfunction "VSTB_28") (pintype "passive"))
    )
  )
)
